# BergProbe-Adapter.net
KiCad netlist of a schematic drawn in EAGLE
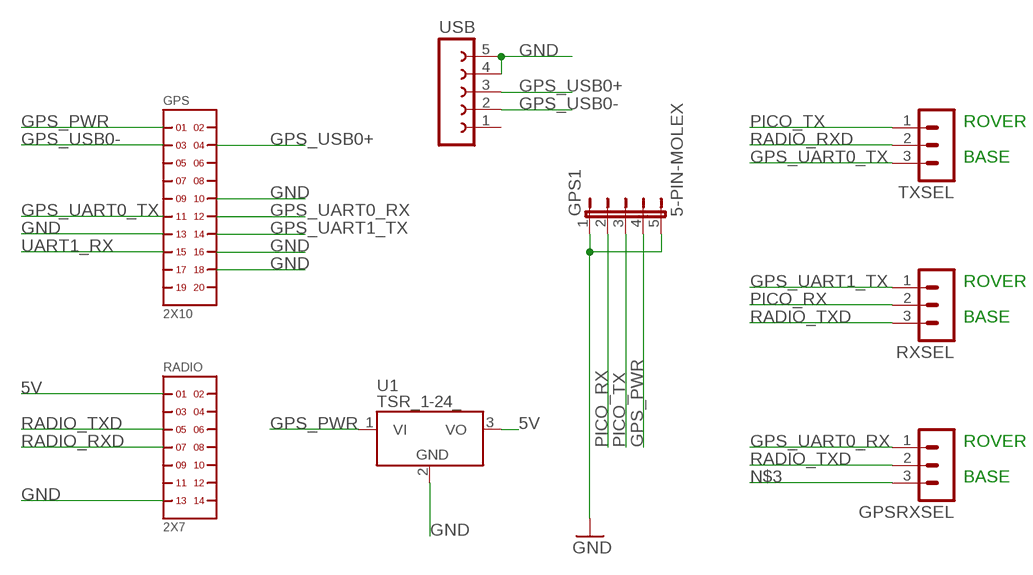
[diagram p0: schematic, sheet 1]

(export (version "E")
  (design (tool "Eeschema 10.0.6"))
  (components
    (comp (ref "GPS")
      (value "2X10")
      (footprint "eagle-import:2X10")
      (libsource (lib "eagle-import") (part "2X10"))
    )
    (comp (ref "GPS1")
      (value "5-PIN-MOLEX")
      (footprint "eagle-import:5-MOLEX")
      (libsource (lib "eagle-import") (part "5-PIN-MOLEX"))
    )
    (comp (ref "GPSRXSEL")
      (value "MA03-1")
      (footprint "eagle-import:MA03-1")
      (libsource (lib "eagle-import") (part "MA03-1"))
    )
    (comp (ref "RADIO")
      (value "2X7")
      (footprint "eagle-import:2X7")
      (libsource (lib "eagle-import") (part "2X7"))
    )
    (comp (ref "RXSEL")
      (value "MA03-1")
      (footprint "eagle-import:MA03-1")
      (libsource (lib "eagle-import") (part "MA03-1"))
    )
    (comp (ref "TXSEL")
      (value "MA03-1")
      (footprint "eagle-import:MA03-1")
      (libsource (lib "eagle-import") (part "MA03-1"))
    )
    (comp (ref "U1")
      (value "TSR_1-24_")
      (footprint "eagle-import:TSR-1")
      (libsource (lib "eagle-import") (part "TSR_1-24_"))
    )
    (comp (ref "USB")
      (value "FE05-1")
      (footprint "eagle-import:FE05-1")
      (libsource (lib "eagle-import") (part "FE05-1"))
    )
  )
  (nets
    (net (code "1") (name "/5V") (class "Default")
      (node (ref "RADIO") (pin "1") (pinfunction "1_1") (pintype "bidirectional"))
      (node (ref "U1") (pin "3") (pinfunction "VO_3") (pintype "power_in"))
    )
    (net (code "2") (name "/GPS_PWR") (class "Default")
      (node (ref "GPS") (pin "1") (pinfunction "1_1") (pintype "bidirectional"))
      (node (ref "GPS1") (pin "4") (pinfunction "4_4") (pintype "passive"))
      (node (ref "U1") (pin "1") (pinfunction "VI_1") (pintype "power_in"))
    )
    (net (code "3") (name "/GPS_UART0_RX") (class "Default")
      (node (ref "GPS") (pin "12") (pinfunction "12_12") (pintype "bidirectional"))
      (node (ref "GPSRXSEL") (pin "1") (pinfunction "1_1") (pintype "passive"))
    )
    (net (code "4") (name "/GPS_UART0_TX") (class "Default")
      (node (ref "GPS") (pin "11") (pinfunction "11_11") (pintype "bidirectional"))
      (node (ref "TXSEL") (pin "3") (pinfunction "3_3") (pintype "passive"))
    )
    (net (code "5") (name "/GPS_UART1_TX") (class "Default")
      (node (ref "GPS") (pin "14") (pinfunction "14_14") (pintype "bidirectional"))
      (node (ref "RXSEL") (pin "1") (pinfunction "1_1") (pintype "passive"))
    )
    (net (code "6") (name "/GPS_USB0+") (class "Default")
      (node (ref "GPS") (pin "4") (pinfunction "4_4") (pintype "bidirectional"))
      (node (ref "USB") (pin "3") (pinfunction "3_3") (pintype "passive"))
    )
    (net (code "7") (name "/GPS_USB0-") (class "Default")
      (node (ref "GPS") (pin "3") (pinfunction "3_3") (pintype "bidirectional"))
      (node (ref "USB") (pin "2") (pinfunction "2_2") (pintype "passive"))
    )
    (net (code "8") (name "/N$3") (class "Default")
      (node (ref "GPSRXSEL") (pin "3") (pinfunction "3_3") (pintype "passive"))
    )
    (net (code "9") (name "/PICO_RX") (class "Default")
      (node (ref "GPS1") (pin "2") (pinfunction "2_2") (pintype "passive"))
      (node (ref "RXSEL") (pin "2") (pinfunction "2_2") (pintype "passive"))
    )
    (net (code "10") (name "/PICO_TX") (class "Default")
      (node (ref "GPS1") (pin "3") (pinfunction "3_3") (pintype "passive"))
      (node (ref "TXSEL") (pin "1") (pinfunction "1_1") (pintype "passive"))
    )
    (net (code "11") (name "/RADIO_RXD") (class "Default")
      (node (ref "RADIO") (pin "7") (pinfunction "7_7") (pintype "bidirectional"))
      (node (ref "TXSEL") (pin "2") (pinfunction "2_2") (pintype "passive"))
    )
    (net (code "12") (name "/RADIO_TXD") (class "Default")
      (node (ref "GPSRXSEL") (pin "2") (pinfunction "2_2") (pintype "passive"))
      (node (ref "RADIO") (pin "5") (pinfunction "5_5") (pintype "bidirectional"))
      (node (ref "RXSEL") (pin "3") (pinfunction "3_3") (pintype "passive"))
    )
    (net (code "13") (name "/UART1_RX") (class "Default")
      (node (ref "GPS") (pin "15") (pinfunction "15_15") (pintype "bidirectional"))
    )
    (net (code "14") (name "GND") (class "Default")
      (node (ref "GPS") (pin "10") (pinfunction "10_10") (pintype "bidirectional"))
      (node (ref "GPS") (pin "13") (pinfunction "13_13") (pintype "bidirectional"))
      (node (ref "GPS") (pin "16") (pinfunction "16_16") (pintype "bidirectional"))
      (node (ref "GPS") (pin "18") (pinfunction "18_18") (pintype "bidirectional"))
      (node (ref "GPS1") (pin "1") (pinfunction "1_1") (pintype "passive"))
      (node (ref "GPS1") (pin "5") (pinfunction "6_5") (pintype "passive"))
      (node (ref "RADIO") (pin "13") (pinfunction "13_13") (pintype "bidirectional"))
      (node (ref "U1") (pin "2") (pinfunction "GND_2") (pintype "power_in"))
      (node (ref "USB") (pin "4") (pinfunction "4_4") (pintype "passive"))
      (node (ref "USB") (pin "5") (pinfunction "5_5") (pintype "passive"))
    )
    (net (code "15") (name "unconnected-(GPS-Pad2)") (class "Default")
      (node (ref "GPS") (pin "2") (pinfunction "2_2") (pintype "bidirectional"))
    )
    (net (code "16") (name "unconnected-(GPS-Pad5)") (class "Default")
      (node (ref "GPS") (pin "5") (pinfunction "5_5") (pintype "bidirectional"))
    )
    (net (code "17") (name "unconnected-(GPS-Pad6)") (class "Default")
      (node (ref "GPS") (pin "6") (pinfunction "6_6") (pintype "bidirectional"))
    )
    (net (code "18") (name "unconnected-(GPS-Pad7)") (class "Default")
      (node (ref "GPS") (pin "7") (pinfunction "7_7") (pintype "bidirectional"))
    )
    (net (code "19") (name "unconnected-(GPS-Pad8)") (class "Default")
      (node (ref "GPS") (pin "8") (pinfunction "8_8") (pintype "bidirectional"))
    )
    (net (code "20") (name "unconnected-(GPS-Pad9)") (class "Default")
      (node (ref "GPS") (pin "9") (pinfunction "9_9") (pintype "bidirectional"))
    )
    (net (code "21") (name "unconnected-(GPS-Pad17)") (class "Default")
      (node (ref "GPS") (pin "17") (pinfunction "17_17") (pintype "bidirectional"))
    )
    (net (code "22") (name "unconnected-(GPS-Pad19)") (class "Default")
      (node (ref "GPS") (pin "19") (pinfunction "19_19") (pintype "bidirectional"))
    )
    (net (code "23") (name "unconnected-(GPS-Pad20)") (class "Default")
      (node (ref "GPS") (pin "20") (pinfunction "20_20") (pintype "bidirectional"))
    )
    (net (code "24") (name "unconnected-(RADIO-Pad2)") (class "Default")
      (node (ref "RADIO") (pin "2") (pinfunction "2_2") (pintype "bidirectional"))
    )
    (net (code "25") (name "unconnected-(RADIO-Pad3)") (class "Default")
      (node (ref "RADIO") (pin "3") (pinfunction "3_3") (pintype "bidirectional"))
    )
    (net (code "26") (name "unconnected-(RADIO-Pad4)") (class "Default")
      (node (ref "RADIO") (pin "4") (pinfunction "4_4") (pintype "bidirectional"))
    )
    (net (code "27") (name "unconnected-(RADIO-Pad6)") (class "Default")
      (node (ref "RADIO") (pin "6") (pinfunction "6_6") (pintype "bidirectional"))
    )
    (net (code "28") (name "unconnected-(RADIO-Pad8)") (class "Default")
      (node (ref "RADIO") (pin "8") (pinfunction "8_8") (pintype "bidirectional"))
    )
    (net (code "29") (name "unconnected-(RADIO-Pad9)") (class "Default")
      (node (ref "RADIO") (pin "9") (pinfunction "9_9") (pintype "bidirectional"))
    )
    (net (code "30") (name "unconnected-(RADIO-Pad10)") (class "Default")
      (node (ref "RADIO") (pin "10") (pinfunction "10_10") (pintype "bidirectional"))
    )
    (net (code "31") (name "unconnected-(RADIO-Pad11)") (class "Default")
      (node (ref "RADIO") (pin "11") (pinfunction "11_11") (pintype "bidirectional"))
    )
    (net (code "32") (name "unconnected-(RADIO-Pad12)") (class "Default")
      (node (ref "RADIO") (pin "12") (pinfunction "12_12") (pintype "bidirectional"))
    )
    (net (code "33") (name "unconnected-(RADIO-Pad14)") (class "Default")
      (node (ref "RADIO") (pin "14") (pinfunction "14_14") (pintype "bidirectional"))
    )
    (net (code "34") (name "unconnected-(USB-Pad1)") (class "Default")
      (node (ref "USB") (pin "1") (pinfunction "1_1") (pintype "passive"))
    )
  )
)
